# 2_MPC555.net
KiCad netlist of a schematic drawn in Altium Designer
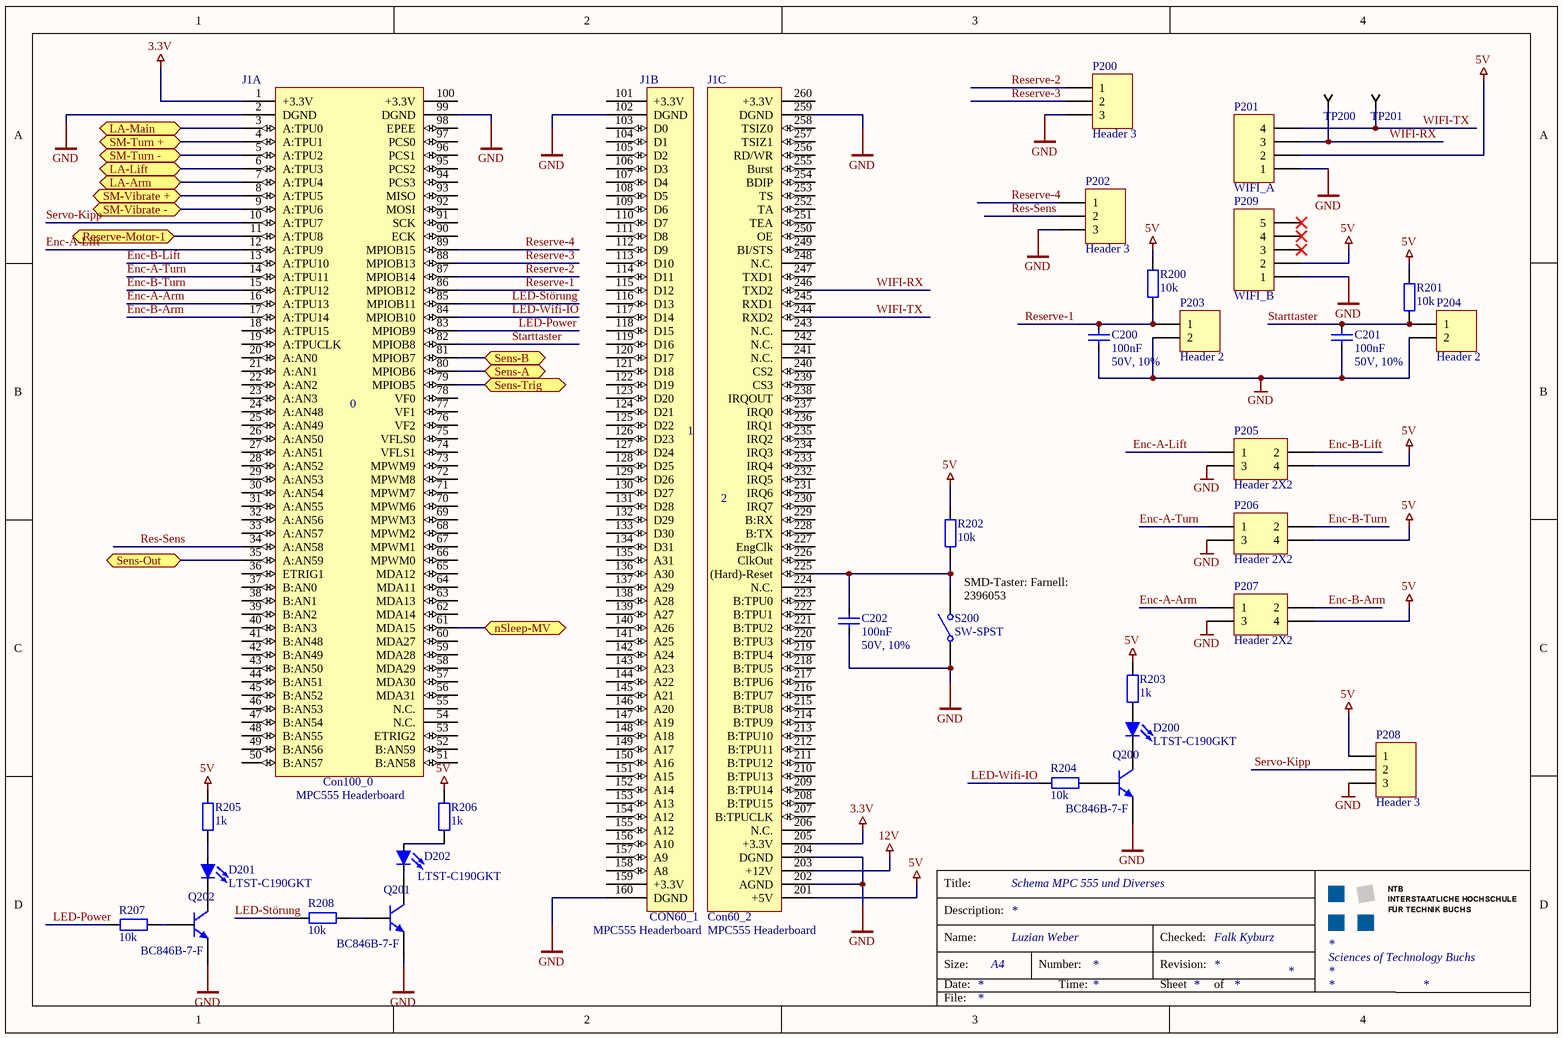
[diagram p0: 2_MPC555.SchDoc]

(export (version "E")
  (design (tool "Eeschema 10.0.6"))
  (components
    (comp (ref "C200")
      (value "100nF")
      (footprint "CAP-0805[2012]")
      (description "100n 50V X7R MLCC 0805 (1608 Metric)")
      (fields (field (name "TOLERANCE") "10%") (field (name "VALADDON") "50V, 10%"))
      (libsource (lib "IR-Sensor") (part "MLCC 0805 100n 50V"))
    )
    (comp (ref "C201")
      (value "100nF")
      (footprint "CAP-0805[2012]")
      (description "100n 50V X7R MLCC 0805 (1608 Metric)")
      (fields (field (name "TOLERANCE") "10%") (field (name "VALADDON") "50V, 10%"))
      (libsource (lib "IR-Sensor") (part "MLCC 0805 100n 50V"))
    )
    (comp (ref "C202")
      (value "100nF")
      (footprint "CAP-0805[2012]")
      (description "100n 50V X7R MLCC 0805 (1608 Metric)")
      (fields (field (name "TOLERANCE") "10%") (field (name "VALADDON") "50V, 10%"))
      (libsource (lib "IR-Sensor") (part "MLCC 0805 100n 50V"))
    )
    (comp (ref "D200")
      (value "LTST-C190GKT")
      (footprint "LED 0603 green")
      (description "LED SMD 0603 green 6mcd")
      (libsource (lib "IR-Sensor") (part "LED Green"))
    )
    (comp (ref "D201")
      (value "LTST-C190GKT")
      (footprint "LED 0603 green")
      (description "LED SMD 0603 green 6mcd")
      (libsource (lib "IR-Sensor") (part "LED Green"))
    )
    (comp (ref "D202")
      (value "LTST-C190GKT")
      (footprint "LED 0603 green")
      (description "LED SMD 0603 green 6mcd")
      (libsource (lib "IR-Sensor") (part "LED Green"))
    )
    (comp (ref "J1")
      (value "MPC555 Headerboard")
      (footprint "MPC555 Headerboard THT")
      (description "NTB MPC555 Headerboard")
      (libsource (lib "ch.ntb.inf.altiumlib_2011-02-10") (part "MPC555 Headerboard"))
    )
    (comp (ref "P200")
      (value "Header 3")
      (footprint "HDR1X3")
      (description "Header, 3-Pin")
      (fields (field (name "PUBLISHER") "Altium Limited"))
      (libsource (lib "Miscellaneous Connectors") (part "Header 3"))
    )
    (comp (ref "P201")
      (value "WIFI_A")
      (footprint "HDR1X4")
      (description "Header, 4-Pin")
      (fields (field (name "PUBLISHER") "Altium Limited"))
      (libsource (lib "Miscellaneous Connectors") (part "Header 4"))
    )
    (comp (ref "P202")
      (value "Header 3")
      (footprint "HDR1X3")
      (description "Header, 3-Pin")
      (fields (field (name "PUBLISHER") "Altium Limited"))
      (libsource (lib "Miscellaneous Connectors") (part "Header 3"))
    )
    (comp (ref "P203")
      (value "Header 2")
      (footprint "HDR1X2")
      (description "Header, 2-Pin")
      (fields (field (name "PUBLISHER") "Altium Limited"))
      (libsource (lib "Miscellaneous Connectors") (part "Header 2"))
    )
    (comp (ref "P204")
      (value "Header 2")
      (footprint "HDR1X2")
      (description "Header, 2-Pin")
      (fields (field (name "PUBLISHER") "Altium Limited"))
      (libsource (lib "Miscellaneous Connectors") (part "Header 2"))
    )
    (comp (ref "P205")
      (value "Header 2X2")
      (footprint "HDR2X2")
      (description "Header, 2-Pin, Dual row")
      (fields (field (name "PUBLISHER") "Altium Limited"))
      (libsource (lib "Miscellaneous Connectors") (part "Header 2X2"))
    )
    (comp (ref "P206")
      (value "Header 2X2")
      (footprint "HDR2X2")
      (description "Header, 2-Pin, Dual row")
      (fields (field (name "PUBLISHER") "Altium Limited"))
      (libsource (lib "Miscellaneous Connectors") (part "Header 2X2"))
    )
    (comp (ref "P207")
      (value "Header 2X2")
      (footprint "HDR2X2")
      (description "Header, 2-Pin, Dual row")
      (fields (field (name "PUBLISHER") "Altium Limited"))
      (libsource (lib "Miscellaneous Connectors") (part "Header 2X2"))
    )
    (comp (ref "P208")
      (value "Header 3")
      (footprint "HDR1X3")
      (description "Header, 3-Pin")
      (fields (field (name "PUBLISHER") "Altium Limited"))
      (libsource (lib "Miscellaneous Connectors") (part "Header 3"))
    )
    (comp (ref "P209")
      (value "WIFI_B")
      (footprint "HDR1X5")
      (description "Header, 5-Pin")
      (fields (field (name "PUBLISHER") "Altium Limited"))
      (libsource (lib "Miscellaneous Connectors") (part "Header 5"))
    )
    (comp (ref "Q200")
      (value "BC846B-7-F")
      (footprint "SOT-23")
      (description "NPN General-purpose Transistor")
      (fields (field (name "MANUFACTURER") "DIODES INC") (field (name "PUBLISHER") "Altium Limited"))
      (libsource (lib "IR-Sensor") (part "BC846B-SOT23"))
    )
    (comp (ref "Q201")
      (value "BC846B-7-F")
      (footprint "SOT-23")
      (description "NPN General-purpose Transistor")
      (fields (field (name "MANUFACTURER") "DIODES INC") (field (name "PUBLISHER") "Altium Limited"))
      (libsource (lib "IR-Sensor") (part "BC846B-SOT23"))
    )
    (comp (ref "Q202")
      (value "BC846B-7-F")
      (footprint "SOT-23")
      (description "NPN General-purpose Transistor")
      (fields (field (name "MANUFACTURER") "DIODES INC") (field (name "PUBLISHER") "Altium Limited"))
      (libsource (lib "IR-Sensor") (part "BC846B-SOT23"))
    )
    (comp (ref "R200")
      (value "10k")
      (footprint "RES-0805[2012]")
      (description "0805 (2013 Metric) 1/10 W 10K 1 Thick Film Chip Resistor")
      (fields (field (name "POWER") "1/10 W") (field (name "TOLERANCE") "1%"))
      (libsource (lib "IR-Sensor") (part "RES 0805"))
    )
    (comp (ref "R201")
      (value "10k")
      (footprint "RES-0805[2012]")
      (description "0805 (2013 Metric) 1/10 W 10K 1 Thick Film Chip Resistor")
      (fields (field (name "POWER") "1/10 W") (field (name "TOLERANCE") "1%"))
      (libsource (lib "IR-Sensor") (part "RES 0805"))
    )
    (comp (ref "R202")
      (value "10k")
      (footprint "RES-0805[2012]")
      (description "0805 (2013 Metric) 1/10 W 10K 1 Thick Film Chip Resistor")
      (fields (field (name "POWER") "1/10 W") (field (name "TOLERANCE") "1%"))
      (libsource (lib "IR-Sensor") (part "RES 0805"))
    )
    (comp (ref "R203")
      (value "1k")
      (footprint "RES-0805[2012]")
      (description "0805 (2013 Metric) 1/10 W 10K 1 Thick Film Chip Resistor")
      (fields (field (name "POWER") "1/10 W") (field (name "TOLERANCE") "1%"))
      (libsource (lib "IR-Sensor") (part "RES 0805"))
    )
    (comp (ref "R204")
      (value "10k")
      (footprint "RES-0805[2012]")
      (description "0805 (2013 Metric) 1/10 W 10K 1 Thick Film Chip Resistor")
      (fields (field (name "POWER") "1/10 W") (field (name "TOLERANCE") "1%"))
      (libsource (lib "IR-Sensor") (part "RES 0805"))
    )
    (comp (ref "R205")
      (value "1k")
      (footprint "RES-0805[2012]")
      (description "0805 (2013 Metric) 1/10 W 10K 1 Thick Film Chip Resistor")
      (fields (field (name "POWER") "1/10 W") (field (name "TOLERANCE") "1%"))
      (libsource (lib "IR-Sensor") (part "RES 0805"))
    )
    (comp (ref "R206")
      (value "1k")
      (footprint "RES-0805[2012]")
      (description "0805 (2013 Metric) 1/10 W 10K 1 Thick Film Chip Resistor")
      (fields (field (name "POWER") "1/10 W") (field (name "TOLERANCE") "1%"))
      (libsource (lib "IR-Sensor") (part "RES 0805"))
    )
    (comp (ref "R207")
      (value "10k")
      (footprint "RES-0805[2012]")
      (description "0805 (2013 Metric) 1/10 W 10K 1 Thick Film Chip Resistor")
      (fields (field (name "POWER") "1/10 W") (field (name "TOLERANCE") "1%"))
      (libsource (lib "IR-Sensor") (part "RES 0805"))
    )
    (comp (ref "R208")
      (value "10k")
      (footprint "RES-0805[2012]")
      (description "0805 (2013 Metric) 1/10 W 10K 1 Thick Film Chip Resistor")
      (fields (field (name "POWER") "1/10 W") (field (name "TOLERANCE") "1%"))
      (libsource (lib "IR-Sensor") (part "RES 0805"))
    )
    (comp (ref "S200")
      (value "SW-SPST")
      (footprint "B3SE-1002P")
      (description "Single-Pole, Single-Throw Switch")
      (fields (field (name "PUBLISHER") "Altium Limited"))
      (libsource (lib "Miscellaneous Devices") (part "SW-SPST"))
    )
    (comp (ref "TP200")
      (value "Testpoint SMD 1206")
      (footprint "TP-SMD-1206")
      (description "Testpoint xSmall")
      (libsource (lib "IR-Sensor") (part "Testpoint SMD 1206"))
    )
    (comp (ref "TP201")
      (value "Testpoint SMD 1206")
      (footprint "TP-SMD-1206")
      (description "Testpoint xSmall")
      (libsource (lib "IR-Sensor") (part "Testpoint SMD 1206"))
    )
  )
  (nets
    (net (code "1") (name "/Enc-A-Arm") (class "Default")
      (node (ref "J1") (pin "16") (pinfunction "A:TPU13_16") (pintype "bidirectional"))
      (node (ref "P207") (pin "1") (pinfunction "1_1") (pintype "passive"))
    )
    (net (code "2") (name "/Enc-A-Lift") (class "Default")
      (node (ref "J1") (pin "12") (pinfunction "A:TPU9_12") (pintype "bidirectional"))
      (node (ref "P205") (pin "1") (pinfunction "1_1") (pintype "passive"))
    )
    (net (code "3") (name "/Enc-A-Turn") (class "Default")
      (node (ref "J1") (pin "14") (pinfunction "A:TPU11_14") (pintype "bidirectional"))
      (node (ref "P206") (pin "1") (pinfunction "1_1") (pintype "passive"))
    )
    (net (code "4") (name "/Enc-B-Arm") (class "Default")
      (node (ref "J1") (pin "17") (pinfunction "A:TPU14_17") (pintype "bidirectional"))
      (node (ref "P207") (pin "2") (pinfunction "2_2") (pintype "passive"))
    )
    (net (code "5") (name "/Enc-B-Lift") (class "Default")
      (node (ref "J1") (pin "13") (pinfunction "A:TPU10_13") (pintype "bidirectional"))
      (node (ref "P205") (pin "2") (pinfunction "2_2") (pintype "passive"))
    )
    (net (code "6") (name "/Enc-B-Turn") (class "Default")
      (node (ref "J1") (pin "15") (pinfunction "A:TPU12_15") (pintype "bidirectional"))
      (node (ref "P206") (pin "2") (pinfunction "2_2") (pintype "passive"))
    )
    (net (code "7") (name "/LA-Arm") (class "Default")
      (node (ref "J1") (pin "7") (pinfunction "A:TPU4_7") (pintype "bidirectional"))
    )
    (net (code "8") (name "/LA-Lift") (class "Default")
      (node (ref "J1") (pin "6") (pinfunction "A:TPU3_6") (pintype "bidirectional"))
    )
    (net (code "9") (name "/LA-Main") (class "Default")
      (node (ref "J1") (pin "3") (pinfunction "A:TPU0_3") (pintype "bidirectional"))
    )
    (net (code "10") (name "/LED-Power") (class "Default")
      (node (ref "J1") (pin "83") (pinfunction "MPIOB9_83") (pintype "bidirectional"))
      (node (ref "R207") (pin "1") (pinfunction "1_1") (pintype "passive"))
    )
    (net (code "11") (name "/LED-Störung") (class "Default")
      (node (ref "J1") (pin "85") (pinfunction "MPIOB11_85") (pintype "bidirectional"))
      (node (ref "R208") (pin "1") (pinfunction "1_1") (pintype "passive"))
    )
    (net (code "12") (name "/LED-Wifi-IO") (class "Default")
      (node (ref "J1") (pin "84") (pinfunction "MPIOB10_84") (pintype "bidirectional"))
      (node (ref "R204") (pin "1") (pinfunction "1_1") (pintype "passive"))
    )
    (net (code "13") (name "/Res-Sens") (class "Default")
      (node (ref "J1") (pin "34") (pinfunction "A:AN58_34") (pintype "bidirectional"))
      (node (ref "P202") (pin "2") (pinfunction "2_2") (pintype "passive"))
    )
    (net (code "14") (name "/Reserve-1") (class "Default")
      (node (ref "C200") (pin "2") (pinfunction "Neg_2") (pintype "passive"))
      (node (ref "J1") (pin "86") (pinfunction "MPIOB12_86") (pintype "bidirectional"))
      (node (ref "P203") (pin "1") (pinfunction "1_1") (pintype "passive"))
      (node (ref "R200") (pin "1") (pinfunction "1_1") (pintype "passive"))
    )
    (net (code "15") (name "/Reserve-2") (class "Default")
      (node (ref "J1") (pin "87") (pinfunction "MPIOB14_87") (pintype "bidirectional"))
      (node (ref "P200") (pin "1") (pinfunction "1_1") (pintype "passive"))
    )
    (net (code "16") (name "/Reserve-3") (class "Default")
      (node (ref "J1") (pin "88") (pinfunction "MPIOB13_88") (pintype "bidirectional"))
      (node (ref "P200") (pin "2") (pinfunction "2_2") (pintype "passive"))
    )
    (net (code "17") (name "/Reserve-4") (class "Default")
      (node (ref "J1") (pin "89") (pinfunction "MPIOB15_89") (pintype "bidirectional"))
      (node (ref "P202") (pin "1") (pinfunction "1_1") (pintype "passive"))
    )
    (net (code "18") (name "/Reserve-Motor-1") (class "Default")
      (node (ref "J1") (pin "11") (pinfunction "A:TPU8_11") (pintype "bidirectional"))
    )
    (net (code "19") (name "/SM-Turn +") (class "Default")
      (node (ref "J1") (pin "4") (pinfunction "A:TPU1_4") (pintype "bidirectional"))
    )
    (net (code "20") (name "/SM-Turn -") (class "Default")
      (node (ref "J1") (pin "5") (pinfunction "A:TPU2_5") (pintype "bidirectional"))
    )
    (net (code "21") (name "/SM-Vibrate +") (class "Default")
      (node (ref "J1") (pin "8") (pinfunction "A:TPU5_8") (pintype "bidirectional"))
    )
    (net (code "22") (name "/SM-Vibrate -") (class "Default")
      (node (ref "J1") (pin "9") (pinfunction "A:TPU6_9") (pintype "bidirectional"))
    )
    (net (code "23") (name "/Sens-A") (class "Default")
      (node (ref "J1") (pin "80") (pinfunction "MPIOB6_80") (pintype "bidirectional"))
    )
    (net (code "24") (name "/Sens-B") (class "Default")
      (node (ref "J1") (pin "81") (pinfunction "MPIOB7_81") (pintype "bidirectional"))
    )
    (net (code "25") (name "/Sens-Out") (class "Default")
      (node (ref "J1") (pin "35") (pinfunction "A:AN59_35") (pintype "bidirectional"))
    )
    (net (code "26") (name "/Sens-Trig") (class "Default")
      (node (ref "J1") (pin "79") (pinfunction "MPIOB5_79") (pintype "bidirectional"))
    )
    (net (code "27") (name "/Servo-Kipp") (class "Default")
      (node (ref "J1") (pin "10") (pinfunction "A:TPU7_10") (pintype "bidirectional"))
      (node (ref "P208") (pin "2") (pinfunction "2_2") (pintype "passive"))
    )
    (net (code "28") (name "/Starttaster") (class "Default")
      (node (ref "C201") (pin "2") (pinfunction "Neg_2") (pintype "passive"))
      (node (ref "J1") (pin "82") (pinfunction "MPIOB8_82") (pintype "bidirectional"))
      (node (ref "P204") (pin "1") (pinfunction "1_1") (pintype "passive"))
      (node (ref "R201") (pin "1") (pinfunction "1_1") (pintype "passive"))
    )
    (net (code "29") (name "/WIFI-RX") (class "Default")
      (node (ref "J1") (pin "246") (pinfunction "TXD2_246") (pintype "bidirectional"))
      (node (ref "P201") (pin "3") (pinfunction "3_3") (pintype "passive"))
      (node (ref "TP200") (pin "1") (pinfunction "0_1") (pintype "passive"))
    )
    (net (code "30") (name "/WIFI-TX") (class "Default")
      (node (ref "J1") (pin "244") (pinfunction "RXD2_244") (pintype "bidirectional"))
      (node (ref "P201") (pin "4") (pinfunction "4_4") (pintype "passive"))
      (node (ref "TP201") (pin "1") (pinfunction "0_1") (pintype "passive"))
    )
    (net (code "31") (name "/nSleep-MV") (class "Default")
      (node (ref "J1") (pin "61") (pinfunction "MDA15_61") (pintype "bidirectional"))
    )
    (net (code "32") (name "3.3V") (class "Default")
      (node (ref "J1") (pin "1") (pinfunction "+3.3V_1") (pintype "power_in"))
      (node (ref "J1") (pin "205") (pinfunction "+3.3V_205") (pintype "power_in"))
    )
    (net (code "33") (name "5V") (class "Default")
      (node (ref "J1") (pin "201") (pinfunction "+5V_201") (pintype "power_in"))
      (node (ref "P201") (pin "2") (pinfunction "2_2") (pintype "passive"))
      (node (ref "P205") (pin "4") (pinfunction "4_4") (pintype "passive"))
      (node (ref "P206") (pin "4") (pinfunction "4_4") (pintype "passive"))
      (node (ref "P207") (pin "4") (pinfunction "4_4") (pintype "passive"))
      (node (ref "P208") (pin "1") (pinfunction "1_1") (pintype "passive"))
      (node (ref "P209") (pin "2") (pinfunction "2_2") (pintype "passive"))
      (node (ref "R200") (pin "2") (pinfunction "2_2") (pintype "passive"))
      (node (ref "R201") (pin "2") (pinfunction "2_2") (pintype "passive"))
      (node (ref "R202") (pin "2") (pinfunction "2_2") (pintype "passive"))
      (node (ref "R203") (pin "2") (pinfunction "2_2") (pintype "passive"))
      (node (ref "R205") (pin "2") (pinfunction "2_2") (pintype "passive"))
      (node (ref "R206") (pin "2") (pinfunction "2_2") (pintype "passive"))
    )
    (net (code "34") (name "12V") (class "Default")
      (node (ref "J1") (pin "203") (pinfunction "+12V_203") (pintype "power_in"))
    )
    (net (code "35") (name "GND") (class "Default")
      (node (ref "C200") (pin "1") (pinfunction "Pos_1") (pintype "passive"))
      (node (ref "C201") (pin "1") (pinfunction "Pos_1") (pintype "passive"))
      (node (ref "C202") (pin "1") (pinfunction "Pos_1") (pintype "passive"))
      (node (ref "J1") (pin "102") (pinfunction "DGND_102") (pintype "power_in"))
      (node (ref "J1") (pin "160") (pinfunction "DGND_160") (pintype "power_in"))
      (node (ref "J1") (pin "2") (pinfunction "DGND_2") (pintype "power_in"))
      (node (ref "J1") (pin "202") (pinfunction "AGND_202") (pintype "power_in"))
      (node (ref "J1") (pin "204") (pinfunction "DGND_204") (pintype "power_in"))
      (node (ref "J1") (pin "259") (pinfunction "DGND_259") (pintype "power_in"))
      (node (ref "J1") (pin "99") (pinfunction "DGND_99") (pintype "power_in"))
      (node (ref "P200") (pin "3") (pinfunction "3_3") (pintype "passive"))
      (node (ref "P201") (pin "1") (pinfunction "1_1") (pintype "passive"))
      (node (ref "P202") (pin "3") (pinfunction "3_3") (pintype "passive"))
      (node (ref "P203") (pin "2") (pinfunction "2_2") (pintype "passive"))
      (node (ref "P204") (pin "2") (pinfunction "2_2") (pintype "passive"))
      (node (ref "P205") (pin "3") (pinfunction "3_3") (pintype "passive"))
      (node (ref "P206") (pin "3") (pinfunction "3_3") (pintype "passive"))
      (node (ref "P207") (pin "3") (pinfunction "3_3") (pintype "passive"))
      (node (ref "P208") (pin "3") (pinfunction "3_3") (pintype "passive"))
      (node (ref "P209") (pin "1") (pinfunction "1_1") (pintype "passive"))
      (node (ref "Q200") (pin "2") (pinfunction "E_2") (pintype "passive"))
      (node (ref "Q201") (pin "2") (pinfunction "E_2") (pintype "passive"))
      (node (ref "Q202") (pin "2") (pinfunction "E_2") (pintype "passive"))
      (node (ref "S200") (pin "1") (pinfunction "COMMON_1") (pintype "passive"))
    )
    (net (code "36") (name "Net-(C202-Neg)") (class "Default")
      (node (ref "C202") (pin "2") (pinfunction "Neg_2") (pintype "passive"))
      (node (ref "J1") (pin "225") (pinfunction "(Hard)-Reset_225") (pintype "bidirectional"))
      (node (ref "R202") (pin "1") (pinfunction "1_1") (pintype "passive"))
      (node (ref "S200") (pin "2") (pinfunction "NO_2") (pintype "passive"))
    )
    (net (code "37") (name "Net-(D200-A)") (class "Default")
      (node (ref "D200") (pin "2") (pinfunction "A_2") (pintype "passive"))
      (node (ref "R203") (pin "1") (pinfunction "1_1") (pintype "passive"))
    )
    (net (code "38") (name "Net-(D200-K)") (class "Default")
      (node (ref "D200") (pin "1") (pinfunction "K_1") (pintype "passive"))
      (node (ref "Q200") (pin "3") (pinfunction "C_3") (pintype "passive"))
    )
    (net (code "39") (name "Net-(D201-A)") (class "Default")
      (node (ref "D201") (pin "2") (pinfunction "A_2") (pintype "passive"))
      (node (ref "R205") (pin "1") (pinfunction "1_1") (pintype "passive"))
    )
    (net (code "40") (name "Net-(D201-K)") (class "Default")
      (node (ref "D201") (pin "1") (pinfunction "K_1") (pintype "passive"))
      (node (ref "Q202") (pin "3") (pinfunction "C_3") (pintype "passive"))
    )
    (net (code "41") (name "Net-(D202-A)") (class "Default")
      (node (ref "D202") (pin "2") (pinfunction "A_2") (pintype "passive"))
      (node (ref "R206") (pin "1") (pinfunction "1_1") (pintype "passive"))
    )
    (net (code "42") (name "Net-(D202-K)") (class "Default")
      (node (ref "D202") (pin "1") (pinfunction "K_1") (pintype "passive"))
      (node (ref "Q201") (pin "3") (pinfunction "C_3") (pintype "passive"))
    )
    (net (code "43") (name "Net-(Q200-B)") (class "Default")
      (node (ref "Q200") (pin "1") (pinfunction "B_1") (pintype "passive"))
      (node (ref "R204") (pin "2") (pinfunction "2_2") (pintype "passive"))
    )
    (net (code "44") (name "Net-(Q201-B)") (class "Default")
      (node (ref "Q201") (pin "1") (pinfunction "B_1") (pintype "passive"))
      (node (ref "R208") (pin "2") (pinfunction "2_2") (pintype "passive"))
    )
    (net (code "45") (name "Net-(Q202-B)") (class "Default")
      (node (ref "Q202") (pin "1") (pinfunction "B_1") (pintype "passive"))
      (node (ref "R207") (pin "2") (pinfunction "2_2") (pintype "passive"))
    )
    (net (code "46") (name "unconnected-(J1A-+3.3V-Pad100)") (class "Default")
      (node (ref "J1") (pin "100") (pinfunction "+3.3V_100") (pintype "power_in"))
    )
    (net (code "47") (name "unconnected-(J1A-A:AN0-Pad20)") (class "Default")
      (node (ref "J1") (pin "20") (pinfunction "A:AN0_20") (pintype "bidirectional"))
    )
    (net (code "48") (name "unconnected-(J1A-A:AN1-Pad21)") (class "Default")
      (node (ref "J1") (pin "21") (pinfunction "A:AN1_21") (pintype "bidirectional"))
    )
    (net (code "49") (name "unconnected-(J1A-A:AN2-Pad22)") (class "Default")
      (node (ref "J1") (pin "22") (pinfunction "A:AN2_22") (pintype "bidirectional"))
    )
    (net (code "50") (name "unconnected-(J1A-A:AN3-Pad23)") (class "Default")
      (node (ref "J1") (pin "23") (pinfunction "A:AN3_23") (pintype "bidirectional"))
    )
    (net (code "51") (name "unconnected-(J1A-A:AN48-Pad24)") (class "Default")
      (node (ref "J1") (pin "24") (pinfunction "A:AN48_24") (pintype "bidirectional"))
    )
    (net (code "52") (name "unconnected-(J1A-A:AN49-Pad25)") (class "Default")
      (node (ref "J1") (pin "25") (pinfunction "A:AN49_25") (pintype "bidirectional"))
    )
    (net (code "53") (name "unconnected-(J1A-A:AN50-Pad26)") (class "Default")
      (node (ref "J1") (pin "26") (pinfunction "A:AN50_26") (pintype "bidirectional"))
    )
    (net (code "54") (name "unconnected-(J1A-A:AN51-Pad27)") (class "Default")
      (node (ref "J1") (pin "27") (pinfunction "A:AN51_27") (pintype "bidirectional"))
    )
    (net (code "55") (name "unconnected-(J1A-A:AN52-Pad28)") (class "Default")
      (node (ref "J1") (pin "28") (pinfunction "A:AN52_28") (pintype "bidirectional"))
    )
    (net (code "56") (name "unconnected-(J1A-A:AN53-Pad29)") (class "Default")
      (node (ref "J1") (pin "29") (pinfunction "A:AN53_29") (pintype "bidirectional"))
    )
    (net (code "57") (name "unconnected-(J1A-A:AN54-Pad30)") (class "Default")
      (node (ref "J1") (pin "30") (pinfunction "A:AN54_30") (pintype "bidirectional"))
    )
    (net (code "58") (name "unconnected-(J1A-A:AN55-Pad31)") (class "Default")
      (node (ref "J1") (pin "31") (pinfunction "A:AN55_31") (pintype "bidirectional"))
    )
    (net (code "59") (name "unconnected-(J1A-A:AN56-Pad32)") (class "Default")
      (node (ref "J1") (pin "32") (pinfunction "A:AN56_32") (pintype "bidirectional"))
    )
    (net (code "60") (name "unconnected-(J1A-A:AN57-Pad33)") (class "Default")
      (node (ref "J1") (pin "33") (pinfunction "A:AN57_33") (pintype "bidirectional"))
    )
    (net (code "61") (name "unconnected-(J1A-A:TPU15-Pad18)") (class "Default")
      (node (ref "J1") (pin "18") (pinfunction "A:TPU15_18") (pintype "bidirectional"))
    )
    (net (code "62") (name "unconnected-(J1A-A:TPUCLK-Pad19)") (class "Default")
      (node (ref "J1") (pin "19") (pinfunction "A:TPUCLK_19") (pintype "bidirectional"))
    )
    (net (code "63") (name "unconnected-(J1A-B:AN0-Pad37)") (class "Default")
      (node (ref "J1") (pin "37") (pinfunction "B:AN0_37") (pintype "bidirectional"))
    )
    (net (code "64") (name "unconnected-(J1A-B:AN1-Pad38)") (class "Default")
      (node (ref "J1") (pin "38") (pinfunction "B:AN1_38") (pintype "bidirectional"))
    )
    (net (code "65") (name "unconnected-(J1A-B:AN2-Pad39)") (class "Default")
      (node (ref "J1") (pin "39") (pinfunction "B:AN2_39") (pintype "bidirectional"))
    )
    (net (code "66") (name "unconnected-(J1A-B:AN3-Pad40)") (class "Default")
      (node (ref "J1") (pin "40") (pinfunction "B:AN3_40") (pintype "bidirectional"))
    )
    (net (code "67") (name "unconnected-(J1A-B:AN48-Pad41)") (class "Default")
      (node (ref "J1") (pin "41") (pinfunction "B:AN48_41") (pintype "bidirectional"))
    )
    (net (code "68") (name "unconnected-(J1A-B:AN49-Pad42)") (class "Default")
      (node (ref "J1") (pin "42") (pinfunction "B:AN49_42") (pintype "bidirectional"))
    )
    (net (code "69") (name "unconnected-(J1A-B:AN50-Pad43)") (class "Default")
      (node (ref "J1") (pin "43") (pinfunction "B:AN50_43") (pintype "bidirectional"))
    )
    (net (code "70") (name "unconnected-(J1A-B:AN51-Pad44)") (class "Default")
      (node (ref "J1") (pin "44") (pinfunction "B:AN51_44") (pintype "bidirectional"))
    )
    (net (code "71") (name "unconnected-(J1A-B:AN52-Pad45)") (class "Default")
      (node (ref "J1") (pin "45") (pinfunction "B:AN52_45") (pintype "bidirectional"))
    )
    (net (code "72") (name "unconnected-(J1A-B:AN53-Pad46)") (class "Default")
      (node (ref "J1") (pin "46") (pinfunction "B:AN53_46") (pintype "bidirectional"))
    )
    (net (code "73") (name "unconnected-(J1A-B:AN54-Pad47)") (class "Default")
      (node (ref "J1") (pin "47") (pinfunction "B:AN54_47") (pintype "bidirectional"))
    )
    (net (code "74") (name "unconnected-(J1A-B:AN55-Pad48)") (class "Default")
      (node (ref "J1") (pin "48") (pinfunction "B:AN55_48") (pintype "bidirectional"))
    )
    (net (code "75") (name "unconnected-(J1A-B:AN56-Pad49)") (class "Default")
      (node (ref "J1") (pin "49") (pinfunction "B:AN56_49") (pintype "bidirectional"))
    )
    (net (code "76") (name "unconnected-(J1A-B:AN57-Pad50)") (class "Default")
      (node (ref "J1") (pin "50") (pinfunction "B:AN57_50") (pintype "bidirectional"))
    )
    (net (code "77") (name "unconnected-(J1A-B:AN58-Pad51)") (class "Default")
      (node (ref "J1") (pin "51") (pinfunction "B:AN58_51") (pintype "bidirectional"))
    )
    (net (code "78") (name "unconnected-(J1A-B:AN59-Pad52)") (class "Default")
      (node (ref "J1") (pin "52") (pinfunction "B:AN59_52") (pintype "bidirectional"))
    )
    (net (code "79") (name "unconnected-(J1A-ECK-Pad90)") (class "Default")
      (node (ref "J1") (pin "90") (pinfunction "ECK_90") (pintype "bidirectional"))
    )
    (net (code "80") (name "unconnected-(J1A-EPEE-Pad98)") (class "Default")
      (node (ref "J1") (pin "98") (pinfunction "EPEE_98") (pintype "bidirectional"))
    )
    (net (code "81") (name "unconnected-(J1A-ETRIG1-Pad36)") (class "Default")
      (node (ref "J1") (pin "36") (pinfunction "ETRIG1_36") (pintype "bidirectional"))
    )
    (net (code "82") (name "unconnected-(J1A-ETRIG2-Pad53)") (class "Default")
      (node (ref "J1") (pin "53") (pinfunction "ETRIG2_53") (pintype "bidirectional"))
    )
    (net (code "83") (name "unconnected-(J1A-MDA11-Pad64)") (class "Default")
      (node (ref "J1") (pin "64") (pinfunction "MDA11_64") (pintype "bidirectional"))
    )
    (net (code "84") (name "unconnected-(J1A-MDA12-Pad65)") (class "Default")
      (node (ref "J1") (pin "65") (pinfunction "MDA12_65") (pintype "bidirectional"))
    )
    (net (code "85") (name "unconnected-(J1A-MDA13-Pad63)") (class "Default")
      (node (ref "J1") (pin "63") (pinfunction "MDA13_63") (pintype "bidirectional"))
    )
    (net (code "86") (name "unconnected-(J1A-MDA14-Pad62)") (class "Default")
      (node (ref "J1") (pin "62") (pinfunction "MDA14_62") (pintype "bidirectional"))
    )
    (net (code "87") (name "unconnected-(J1A-MDA27-Pad60)") (class "Default")
      (node (ref "J1") (pin "60") (pinfunction "MDA27_60") (pintype "bidirectional"))
    )
    (net (code "88") (name "unconnected-(J1A-MDA28-Pad59)") (class "Default")
      (node (ref "J1") (pin "59") (pinfunction "MDA28_59") (pintype "bidirectional"))
    )
    (net (code "89") (name "unconnected-(J1A-MDA29-Pad58)") (class "Default")
      (node (ref "J1") (pin "58") (pinfunction "MDA29_58") (pintype "bidirectional"))
    )
    (net (code "90") (name "unconnected-(J1A-MDA30-Pad57)") (class "Default")
      (node (ref "J1") (pin "57") (pinfunction "MDA30_57") (pintype "bidirectional"))
    )
    (net (code "91") (name "unconnected-(J1A-MDA31-Pad56)") (class "Default")
      (node (ref "J1") (pin "56") (pinfunction "MDA31_56") (pintype "bidirectional"))
    )
    (net (code "92") (name "unconnected-(J1A-MISO-Pad93)") (class "Default")
      (node (ref "J1") (pin "93") (pinfunction "MISO_93") (pintype "bidirectional"))
    )
    (net (code "93") (name "unconnected-(J1A-MOSI-Pad92)") (class "Default")
      (node (ref "J1") (pin "92") (pinfunction "MOSI_92") (pintype "bidirectional"))
    )
    (net (code "94") (name "unconnected-(J1A-MPWM0-Pad66)") (class "Default")
      (node (ref "J1") (pin "66") (pinfunction "MPWM0_66") (pintype "bidirectional"))
    )
    (net (code "95") (name "unconnected-(J1A-MPWM1-Pad67)") (class "Default")
      (node (ref "J1") (pin "67") (pinfunction "MPWM1_67") (pintype "bidirectional"))
    )
    (net (code "96") (name "unconnected-(J1A-MPWM2-Pad68)") (class "Default")
      (node (ref "J1") (pin "68") (pinfunction "MPWM2_68") (pintype "bidirectional"))
    )
    (net (code "97") (name "unconnected-(J1A-MPWM3-Pad69)") (class "Default")
      (node (ref "J1") (pin "69") (pinfunction "MPWM3_69") (pintype "bidirectional"))
    )
    (net (code "98") (name "unconnected-(J1A-MPWM6-Pad70)") (class "Default")
      (node (ref "J1") (pin "70") (pinfunction "MPWM6_70") (pintype "bidirectional"))
    )
    (net (code "99") (name "unconnected-(J1A-MPWM7-Pad71)") (class "Default")
      (node (ref "J1") (pin "71") (pinfunction "MPWM7_71") (pintype "bidirectional"))
    )
    (net (code "100") (name "unconnected-(J1A-MPWM8-Pad72)") (class "Default")
      (node (ref "J1") (pin "72") (pinfunction "MPWM8_72") (pintype "bidirectional"))
    )
    (net (code "101") (name "unconnected-(J1A-MPWM9-Pad73)") (class "Default")
      (node (ref "J1") (pin "73") (pinfunction "MPWM9_73") (pintype "bidirectional"))
    )
    (net (code "102") (name "unconnected-(J1A-N.C.-Pad54)") (class "Default")
      (node (ref "J1") (pin "54") (pinfunction "N.C._54") (pintype "tri_state"))
    )
    (net (code "103") (name "unconnected-(J1A-N.C.-Pad55)") (class "Default")
      (node (ref "J1") (pin "55") (pinfunction "N.C._55") (pintype "tri_state"))
    )
    (net (code "104") (name "unconnected-(J1A-PCS0-Pad97)") (class "Default")
      (node (ref "J1") (pin "97") (pinfunction "PCS0_97") (pintype "bidirectional"))
    )
    (net (code "105") (name "unconnected-(J1A-PCS1-Pad96)") (class "Default")
      (node (ref "J1") (pin "96") (pinfunction "PCS1_96") (pintype "bidirectional"))
    )
    (net (code "106") (name "unconnected-(J1A-PCS2-Pad95)") (class "Default")
      (node (ref "J1") (pin "95") (pinfunction "PCS2_95") (pintype "bidirectional"))
    )
    (net (code "107") (name "unconnected-(J1A-PCS3-Pad94)") (class "Default")
      (node (ref "J1") (pin "94") (pinfunction "PCS3_94") (pintype "bidirectional"))
    )
    (net (code "108") (name "unconnected-(J1A-SCK-Pad91)") (class "Default")
      (node (ref "J1") (pin "91") (pinfunction "SCK_91") (pintype "bidirectional"))
    )
    (net (code "109") (name "unconnected-(J1A-VF0-Pad78)") (class "Default")
      (node (ref "J1") (pin "78") (pinfunction "VF0_78") (pintype "bidirectional"))
    )
    (net (code "110") (name "unconnected-(J1A-VF1-Pad77)") (class "Default")
      (node (ref "J1") (pin "77") (pinfunction "VF1_77") (pintype "bidirectional"))
    )
    (net (code "111") (name "unconnected-(J1A-VF2-Pad76)") (class "Default")
      (node (ref "J1") (pin "76") (pinfunction "VF2_76") (pintype "bidirectional"))
    )
    (net (code "112") (name "unconnected-(J1A-VFLS0-Pad75)") (class "Default")
      (node (ref "J1") (pin "75") (pinfunction "VFLS0_75") (pintype "bidirectional"))
    )
    (net (code "113") (name "unconnected-(J1A-VFLS1-Pad74)") (class "Default")
      (node (ref "J1") (pin "74") (pinfunction "VFLS1_74") (pintype "bidirectional"))
    )
    (net (code "114") (name "unconnected-(J1B-+3.3V-Pad101)") (class "Default")
      (node (ref "J1") (pin "101") (pinfunction "+3.3V_101") (pintype "power_in"))
    )
    (net (code "115") (name "unconnected-(J1B-+3.3V-Pad159)") (class "Default")
      (node (ref "J1") (pin "159") (pinfunction "+3.3V_159") (pintype "power_in"))
    )
    (net (code "116") (name "unconnected-(J1B-A8-Pad158)") (class "Default")
      (node (ref "J1") (pin "158") (pinfunction "A8_158") (pintype "bidirectional"))
    )
    (net (code "117") (name "unconnected-(J1B-A9-Pad157)") (class "Default")
      (node (ref "J1") (pin "157") (pinfunction "A9_157") (pintype "bidirectional"))
    )
    (net (code "118") (name "unconnected-(J1B-A10-Pad156)") (class "Default")
      (node (ref "J1") (pin "156") (pinfunction "A10_156") (pintype "bidirectional"))
    )
    (net (code "119") (name "unconnected-(J1B-A12-Pad154)") (class "Default")
      (node (ref "J1") (pin "154") (pinfunction "A12_154") (pintype "bidirectional"))
    )
    (net (code "120") (name "unconnected-(J1B-A12-Pad155)") (class "Default")
      (node (ref "J1") (pin "155") (pinfunction "A12_155") (pintype "bidirectional"))
    )
    (net (code "121") (name "unconnected-(J1B-A13-Pad153)") (class "Default")
      (node (ref "J1") (pin "153") (pinfunction "A13_153") (pintype "bidirectional"))
    )
    (net (code "122") (name "unconnected-(J1B-A14-Pad152)") (class "Default")
      (node (ref "J1") (pin "152") (pinfunction "A14_152") (pintype "bidirectional"))
    )
    (net (code "123") (name "unconnected-(J1B-A15-Pad151)") (class "Default")
      (node (ref "J1") (pin "151") (pinfunction "A15_151") (pintype "bidirectional"))
    )
    (net (code "124") (name "unconnected-(J1B-A16-Pad150)") (class "Default")
      (node (ref "J1") (pin "150") (pinfunction "A16_150") (pintype "bidirectional"))
    )
    (net (code "125") (name "unconnected-(J1B-A17-Pad149)") (class "Default")
      (node (ref "J1") (pin "149") (pinfunction "A17_149") (pintype "bidirectional"))
    )
    (net (code "126") (name "unconnected-(J1B-A18-Pad148)") (class "Default")
      (node (ref "J1") (pin "148") (pinfunction "A18_148") (pintype "bidirectional"))
    )
    (net (code "127") (name "unconnected-(J1B-A19-Pad147)") (class "Default")
      (node (ref "J1") (pin "147") (pinfunction "A19_147") (pintype "bidirectional"))
    )
    (net (code "128") (name "unconnected-(J1B-A20-Pad146)") (class "Default")
      (node (ref "J1") (pin "146") (pinfunction "A20_146") (pintype "bidirectional"))
    )
    (net (code "129") (name "unconnected-(J1B-A21-Pad145)") (class "Default")
      (node (ref "J1") (pin "145") (pinfunction "A21_145") (pintype "bidirectional"))
    )
    (net (code "130") (name "unconnected-(J1B-A22-Pad144)") (class "Default")
      (node (ref "J1") (pin "144") (pinfunction "A22_144") (pintype "bidirectional"))
    )
    (net (code "131") (name "unconnected-(J1B-A23-Pad143)") (class "Default")
      (node (ref "J1") (pin "143") (pinfunction "A23_143") (pintype "bidirectional"))
    )
    (net (code "132") (name "unconnected-(J1B-A24-Pad142)") (class "Default")
      (node (ref "J1") (pin "142") (pinfunction "A24_142") (pintype "bidirectional"))
    )
    (net (code "133") (name "unconnected-(J1B-A25-Pad141)") (class "Default")
      (node (ref "J1") (pin "141") (pinfunction "A25_141") (pintype "bidirectional"))
    )
    (net (code "134") (name "unconnected-(J1B-A26-Pad140)") (class "Default")
      (node (ref "J1") (pin "140") (pinfunction "A26_140") (pintype "bidirectional"))
    )
    (net (code "135") (name "unconnected-(J1B-A27-Pad139)") (class "Default")
      (node (ref "J1") (pin "139") (pinfunction "A27_139") (pintype "bidirectional"))
    )
    (net (code "136") (name "unconnected-(J1B-A28-Pad138)") (class "Default")
      (node (ref "J1") (pin "138") (pinfunction "A28_138") (pintype "bidirectional"))
    )
    (net (code "137") (name "unconnected-(J1B-A29-Pad137)") (class "Default")
      (node (ref "J1") (pin "137") (pinfunction "A29_137") (pintype "bidirectional"))
    )
    (net (code "138") (name "unconnected-(J1B-A30-Pad136)") (class "Default")
      (node (ref "J1") (pin "136") (pinfunction "A30_136") (pintype "bidirectional"))
    )
    (net (code "139") (name "unconnected-(J1B-A31-Pad135)") (class "Default")
      (node (ref "J1") (pin "135") (pinfunction "A31_135") (pintype "bidirectional"))
    )
    (net (code "140") (name "unconnected-(J1B-D0-Pad103)") (class "Default")
      (node (ref "J1") (pin "103") (pinfunction "D0_103") (pintype "bidirectional"))
    )
    (net (code "141") (name "unconnected-(J1B-D1-Pad104)") (class "Default")
      (node (ref "J1") (pin "104") (pinfunction "D1_104") (pintype "bidirectional"))
    )
    (net (code "142") (name "unconnected-(J1B-D2-Pad105)") (class "Default")
      (node (ref "J1") (pin "105") (pinfunction "D2_105") (pintype "bidirectional"))
    )
    (net (code "143") (name "unconnected-(J1B-D3-Pad106)") (class "Default")
      (node (ref "J1") (pin "106") (pinfunction "D3_106") (pintype "bidirectional"))
    )
    (net (code "144") (name "unconnected-(J1B-D4-Pad107)") (class "Default")
      (node (ref "J1") (pin "107") (pinfunction "D4_107") (pintype "bidirectional"))
    )
    (net (code "145") (name "unconnected-(J1B-D5-Pad108)") (class "Default")
      (node (ref "J1") (pin "108") (pinfunction "D5_108") (pintype "bidirectional"))
    )
    (net (code "146") (name "unconnected-(J1B-D6-Pad109)") (class "Default")
      (node (ref "J1") (pin "109") (pinfunction "D6_109") (pintype "bidirectional"))
    )
    (net (code "147") (name "unconnected-(J1B-D7-Pad110)") (class "Default")
      (node (ref "J1") (pin "110") (pinfunction "D7_110") (pintype "bidirectional"))
    )
    (net (code "148") (name "unconnected-(J1B-D8-Pad111)") (class "Default")
      (node (ref "J1") (pin "111") (pinfunction "D8_111") (pintype "bidirectional"))
    )
    (net (code "149") (name "unconnected-(J1B-D9-Pad112)") (class "Default")
      (node (ref "J1") (pin "112") (pinfunction "D9_112") (pintype "bidirectional"))
    )
    (net (code "150") (name "unconnected-(J1B-D10-Pad113)") (class "Default")
      (node (ref "J1") (pin "113") (pinfunction "D10_113") (pintype "bidirectional"))
    )
    (net (code "151") (name "unconnected-(J1B-D11-Pad114)") (class "Default")
      (node (ref "J1") (pin "114") (pinfunction "D11_114") (pintype "bidirectional"))
    )
    (net (code "152") (name "unconnected-(J1B-D12-Pad115)") (class "Default")
      (node (ref "J1") (pin "115") (pinfunction "D12_115") (pintype "bidirectional"))
    )
    (net (code "153") (name "unconnected-(J1B-D13-Pad116)") (class "Default")
      (node (ref "J1") (pin "116") (pinfunction "D13_116") (pintype "bidirectional"))
    )
    (net (code "154") (name "unconnected-(J1B-D14-Pad117)") (class "Default")
      (node (ref "J1") (pin "117") (pinfunction "D14_117") (pintype "bidirectional"))
    )
    (net (code "155") (name "unconnected-(J1B-D15-Pad118)") (class "Default")
      (node (ref "J1") (pin "118") (pinfunction "D15_118") (pintype "bidirectional"))
    )
    (net (code "156") (name "unconnected-(J1B-D16-Pad119)") (class "Default")
      (node (ref "J1") (pin "119") (pinfunction "D16_119") (pintype "bidirectional"))
    )
    (net (code "157") (name "unconnected-(J1B-D17-Pad120)") (class "Default")
      (node (ref "J1") (pin "120") (pinfunction "D17_120") (pintype "bidirectional"))
    )
    (net (code "158") (name "unconnected-(J1B-D18-Pad121)") (class "Default")
      (node (ref "J1") (pin "121") (pinfunction "D18_121") (pintype "bidirectional"))
    )
    (net (code "159") (name "unconnected-(J1B-D19-Pad122)") (class "Default")
      (node (ref "J1") (pin "122") (pinfunction "D19_122") (pintype "bidirectional"))
    )
    (net (code "160") (name "unconnected-(J1B-D20-Pad123)") (class "Default")
      (node (ref "J1") (pin "123") (pinfunction "D20_123") (pintype "bidirectional"))
    )
    (net (code "161") (name "unconnected-(J1B-D21-Pad124)") (class "Default")
      (node (ref "J1") (pin "124") (pinfunction "D21_124") (pintype "bidirectional"))
    )
    (net (code "162") (name "unconnected-(J1B-D22-Pad125)") (class "Default")
      (node (ref "J1") (pin "125") (pinfunction "D22_125") (pintype "bidirectional"))
    )
    (net (code "163") (name "unconnected-(J1B-D23-Pad126)") (class "Default")
      (node (ref "J1") (pin "126") (pinfunction "D23_126") (pintype "bidirectional"))
    )
    (net (code "164") (name "unconnected-(J1B-D24-Pad127)") (class "Default")
      (node (ref "J1") (pin "127") (pinfunction "D24_127") (pintype "bidirectional"))
    )
    (net (code "165") (name "unconnected-(J1B-D25-Pad128)") (class "Default")
      (node (ref "J1") (pin "128") (pinfunction "D25_128") (pintype "bidirectional"))
    )
    (net (code "166") (name "unconnected-(J1B-D26-Pad129)") (class "Default")
      (node (ref "J1") (pin "129") (pinfunction "D26_129") (pintype "bidirectional"))
    )
    (net (code "167") (name "unconnected-(J1B-D27-Pad130)") (class "Default")
      (node (ref "J1") (pin "130") (pinfunction "D27_130") (pintype "bidirectional"))
    )
    (net (code "168") (name "unconnected-(J1B-D28-Pad131)") (class "Default")
      (node (ref "J1") (pin "131") (pinfunction "D28_131") (pintype "bidirectional"))
    )
    (net (code "169") (name "unconnected-(J1B-D29-Pad132)") (class "Default")
      (node (ref "J1") (pin "132") (pinfunction "D29_132") (pintype "bidirectional"))
    )
    (net (code "170") (name "unconnected-(J1B-D30-Pad133)") (class "Default")
      (node (ref "J1") (pin "133") (pinfunction "D30_133") (pintype "bidirectional"))
    )
    (net (code "171") (name "unconnected-(J1B-D31-Pad134)") (class "Default")
      (node (ref "J1") (pin "134") (pinfunction "D31_134") (pintype "bidirectional"))
    )
    (net (code "172") (name "unconnected-(J1C-+3.3V-Pad260)") (class "Default")
      (node (ref "J1") (pin "260") (pinfunction "+3.3V_260") (pintype "power_in"))
    )
    (net (code "173") (name "unconnected-(J1C-B:RX-Pad229)") (class "Default")
      (node (ref "J1") (pin "229") (pinfunction "B:RX_229") (pintype "bidirectional"))
    )
    (net (code "174") (name "unconnected-(J1C-B:TPU0-Pad223)") (class "Default")
      (node (ref "J1") (pin "223") (pinfunction "B:TPU0_223") (pintype "bidirectional"))
    )
    (net (code "175") (name "unconnected-(J1C-B:TPU1-Pad222)") (class "Default")
      (node (ref "J1") (pin "222") (pinfunction "B:TPU1_222") (pintype "bidirectional"))
    )
    (net (code "176") (name "unconnected-(J1C-B:TPU2-Pad221)") (class "Default")
      (node (ref "J1") (pin "221") (pinfunction "B:TPU2_221") (pintype "bidirectional"))
    )
    (net (code "177") (name "unconnected-(J1C-B:TPU3-Pad220)") (class "Default")
      (node (ref "J1") (pin "220") (pinfunction "B:TPU3_220") (pintype "bidirectional"))
    )
    (net (code "178") (name "unconnected-(J1C-B:TPU4-Pad219)") (class "Default")
      (node (ref "J1") (pin "219") (pinfunction "B:TPU4_219") (pintype "bidirectional"))
    )
    (net (code "179") (name "unconnected-(J1C-B:TPU5-Pad218)") (class "Default")
      (node (ref "J1") (pin "218") (pinfunction "B:TPU5_218") (pintype "bidirectional"))
    )
    (net (code "180") (name "unconnected-(J1C-B:TPU6-Pad217)") (class "Default")
      (node (ref "J1") (pin "217") (pinfunction "B:TPU6_217") (pintype "bidirectional"))
    )
    (net (code "181") (name "unconnected-(J1C-B:TPU7-Pad216)") (class "Default")
      (node (ref "J1") (pin "216") (pinfunction "B:TPU7_216") (pintype "bidirectional"))
    )
    (net (code "182") (name "unconnected-(J1C-B:TPU8-Pad215)") (class "Default")
      (node (ref "J1") (pin "215") (pinfunction "B:TPU8_215") (pintype "bidirectional"))
    )
    (net (code "183") (name "unconnected-(J1C-B:TPU9-Pad214)") (class "Default")
      (node (ref "J1") (pin "214") (pinfunction "B:TPU9_214") (pintype "bidirectional"))
    )
    (net (code "184") (name "unconnected-(J1C-B:TPU10-Pad213)") (class "Default")
      (node (ref "J1") (pin "213") (pinfunction "B:TPU10_213") (pintype "bidirectional"))
    )
    (net (code "185") (name "unconnected-(J1C-B:TPU11-Pad212)") (class "Default")
      (node (ref "J1") (pin "212") (pinfunction "B:TPU11_212") (pintype "bidirectional"))
    )
    (net (code "186") (name "unconnected-(J1C-B:TPU12-Pad211)") (class "Default")
      (node (ref "J1") (pin "211") (pinfunction "B:TPU12_211") (pintype "bidirectional"))
    )
    (net (code "187") (name "unconnected-(J1C-B:TPU13-Pad210)") (class "Default")
      (node (ref "J1") (pin "210") (pinfunction "B:TPU13_210") (pintype "bidirectional"))
    )
    (net (code "188") (name "unconnected-(J1C-B:TPU14-Pad209)") (class "Default")
      (node (ref "J1") (pin "209") (pinfunction "B:TPU14_209") (pintype "bidirectional"))
    )
    (net (code "189") (name "unconnected-(J1C-B:TPU15-Pad208)") (class "Default")
      (node (ref "J1") (pin "208") (pinfunction "B:TPU15_208") (pintype "bidirectional"))
    )
    (net (code "190") (name "unconnected-(J1C-B:TPUCLK-Pad207)") (class "Default")
      (node (ref "J1") (pin "207") (pinfunction "B:TPUCLK_207") (pintype "bidirectional"))
    )
    (net (code "191") (name "unconnected-(J1C-B:TX-Pad228)") (class "Default")
      (node (ref "J1") (pin "228") (pinfunction "B:TX_228") (pintype "bidirectional"))
    )
    (net (code "192") (name "unconnected-(J1C-BDIP-Pad254)") (class "Default")
      (node (ref "J1") (pin "254") (pinfunction "BDIP_254") (pintype "bidirectional"))
    )
    (net (code "193") (name "unconnected-(J1C-BI{slash}STS-Pad249)") (class "Default")
      (node (ref "J1") (pin "249") (pinfunction "BI/STS_249") (pintype "bidirectional"))
    )
    (net (code "194") (name "unconnected-(J1C-Burst-Pad255)") (class "Default")
      (node (ref "J1") (pin "255") (pinfunction "Burst_255") (pintype "bidirectional"))
    )
    (net (code "195") (name "unconnected-(J1C-CS2-Pad240)") (class "Default")
      (node (ref "J1") (pin "240") (pinfunction "CS2_240") (pintype "bidirectional"))
    )
    (net (code "196") (name "unconnected-(J1C-CS3-Pad239)") (class "Default")
      (node (ref "J1") (pin "239") (pinfunction "CS3_239") (pintype "bidirectional"))
    )
    (net (code "197") (name "unconnected-(J1C-ClkOut-Pad226)") (class "Default")
      (node (ref "J1") (pin "226") (pinfunction "ClkOut_226") (pintype "bidirectional"))
    )
    (net (code "198") (name "unconnected-(J1C-EngClk-Pad227)") (class "Default")
      (node (ref "J1") (pin "227") (pinfunction "EngClk_227") (pintype "bidirectional"))
    )
    (net (code "199") (name "unconnected-(J1C-IRQ0-Pad237)") (class "Default")
      (node (ref "J1") (pin "237") (pinfunction "IRQ0_237") (pintype "bidirectional"))
    )
    (net (code "200") (name "unconnected-(J1C-IRQ1-Pad236)") (class "Default")
      (node (ref "J1") (pin "236") (pinfunction "IRQ1_236") (pintype "bidirectional"))
    )
    (net (code "201") (name "unconnected-(J1C-IRQ2-Pad235)") (class "Default")
      (node (ref "J1") (pin "235") (pinfunction "IRQ2_235") (pintype "bidirectional"))
    )
    (net (code "202") (name "unconnected-(J1C-IRQ3-Pad234)") (class "Default")
      (node (ref "J1") (pin "234") (pinfunction "IRQ3_234") (pintype "bidirectional"))
    )
    (net (code "203") (name "unconnected-(J1C-IRQ4-Pad233)") (class "Default")
      (node (ref "J1") (pin "233") (pinfunction "IRQ4_233") (pintype "bidirectional"))
    )
    (net (code "204") (name "unconnected-(J1C-IRQ5-Pad232)") (class "Default")
      (node (ref "J1") (pin "232") (pinfunction "IRQ5_232") (pintype "bidirectional"))
    )
    (net (code "205") (name "unconnected-(J1C-IRQ6-Pad231)") (class "Default")
      (node (ref "J1") (pin "231") (pinfunction "IRQ6_231") (pintype "bidirectional"))
    )
    (net (code "206") (name "unconnected-(J1C-IRQ7-Pad230)") (class "Default")
      (node (ref "J1") (pin "230") (pinfunction "IRQ7_230") (pintype "bidirectional"))
    )
    (net (code "207") (name "unconnected-(J1C-IRQOUT-Pad238)") (class "Default")
      (node (ref "J1") (pin "238") (pinfunction "IRQOUT_238") (pintype "bidirectional"))
    )
    (net (code "208") (name "unconnected-(J1C-N.C.-Pad206)") (class "Default")
      (node (ref "J1") (pin "206") (pinfunction "N.C._206") (pintype "tri_state"))
    )
    (net (code "209") (name "unconnected-(J1C-N.C.-Pad224)") (class "Default")
      (node (ref "J1") (pin "224") (pinfunction "N.C._224") (pintype "tri_state"))
    )
    (net (code "210") (name "unconnected-(J1C-N.C.-Pad241)") (class "Default")
      (node (ref "J1") (pin "241") (pinfunction "N.C._241") (pintype "tri_state"))
    )
    (net (code "211") (name "unconnected-(J1C-N.C.-Pad242)") (class "Default")
      (node (ref "J1") (pin "242") (pinfunction "N.C._242") (pintype "tri_state"))
    )
    (net (code "212") (name "unconnected-(J1C-N.C.-Pad243)") (class "Default")
      (node (ref "J1") (pin "243") (pinfunction "N.C._243") (pintype "tri_state"))
    )
    (net (code "213") (name "unconnected-(J1C-N.C.-Pad248)") (class "Default")
      (node (ref "J1") (pin "248") (pinfunction "N.C._248") (pintype "tri_state"))
    )
    (net (code "214") (name "unconnected-(J1C-OE-Pad250)") (class "Default")
      (node (ref "J1") (pin "250") (pinfunction "OE_250") (pintype "bidirectional"))
    )
    (net (code "215") (name "unconnected-(J1C-RD{slash}WR-Pad256)") (class "Default")
      (node (ref "J1") (pin "256") (pinfunction "RD/WR_256") (pintype "bidirectional"))
    )
    (net (code "216") (name "unconnected-(J1C-RXD1-Pad245)") (class "Default")
      (node (ref "J1") (pin "245") (pinfunction "RXD1_245") (pintype "bidirectional"))
    )
    (net (code "217") (name "unconnected-(J1C-TA-Pad252)") (class "Default")
      (node (ref "J1") (pin "252") (pinfunction "TA_252") (pintype "bidirectional"))
    )
    (net (code "218") (name "unconnected-(J1C-TEA-Pad251)") (class "Default")
      (node (ref "J1") (pin "251") (pinfunction "TEA_251") (pintype "bidirectional"))
    )
    (net (code "219") (name "unconnected-(J1C-TS-Pad253)") (class "Default")
      (node (ref "J1") (pin "253") (pinfunction "TS_253") (pintype "bidirectional"))
    )
    (net (code "220") (name "unconnected-(J1C-TSIZ0-Pad258)") (class "Default")
      (node (ref "J1") (pin "258") (pinfunction "TSIZ0_258") (pintype "bidirectional"))
    )
    (net (code "221") (name "unconnected-(J1C-TSIZ1-Pad257)") (class "Default")
      (node (ref "J1") (pin "257") (pinfunction "TSIZ1_257") (pintype "bidirectional"))
    )
    (net (code "222") (name "unconnected-(J1C-TXD1-Pad247)") (class "Default")
      (node (ref "J1") (pin "247") (pinfunction "TXD1_247") (pintype "bidirectional"))
    )
    (net (code "223") (name "unconnected-(P209-Pad3)") (class "Default")
      (node (ref "P209") (pin "3") (pinfunction "3_3") (pintype "passive+no_connect"))
    )
    (net (code "224") (name "unconnected-(P209-Pad4)") (class "Default")
      (node (ref "P209") (pin "4") (pinfunction "4_4") (pintype "passive+no_connect"))
    )
    (net (code "225") (name "unconnected-(P209-Pad5)") (class "Default")
      (node (ref "P209") (pin "5") (pinfunction "5_5") (pintype "passive+no_connect"))
    )
  )
)
